# Battery_V2.net
KiCad netlist of a schematic drawn in EAGLE
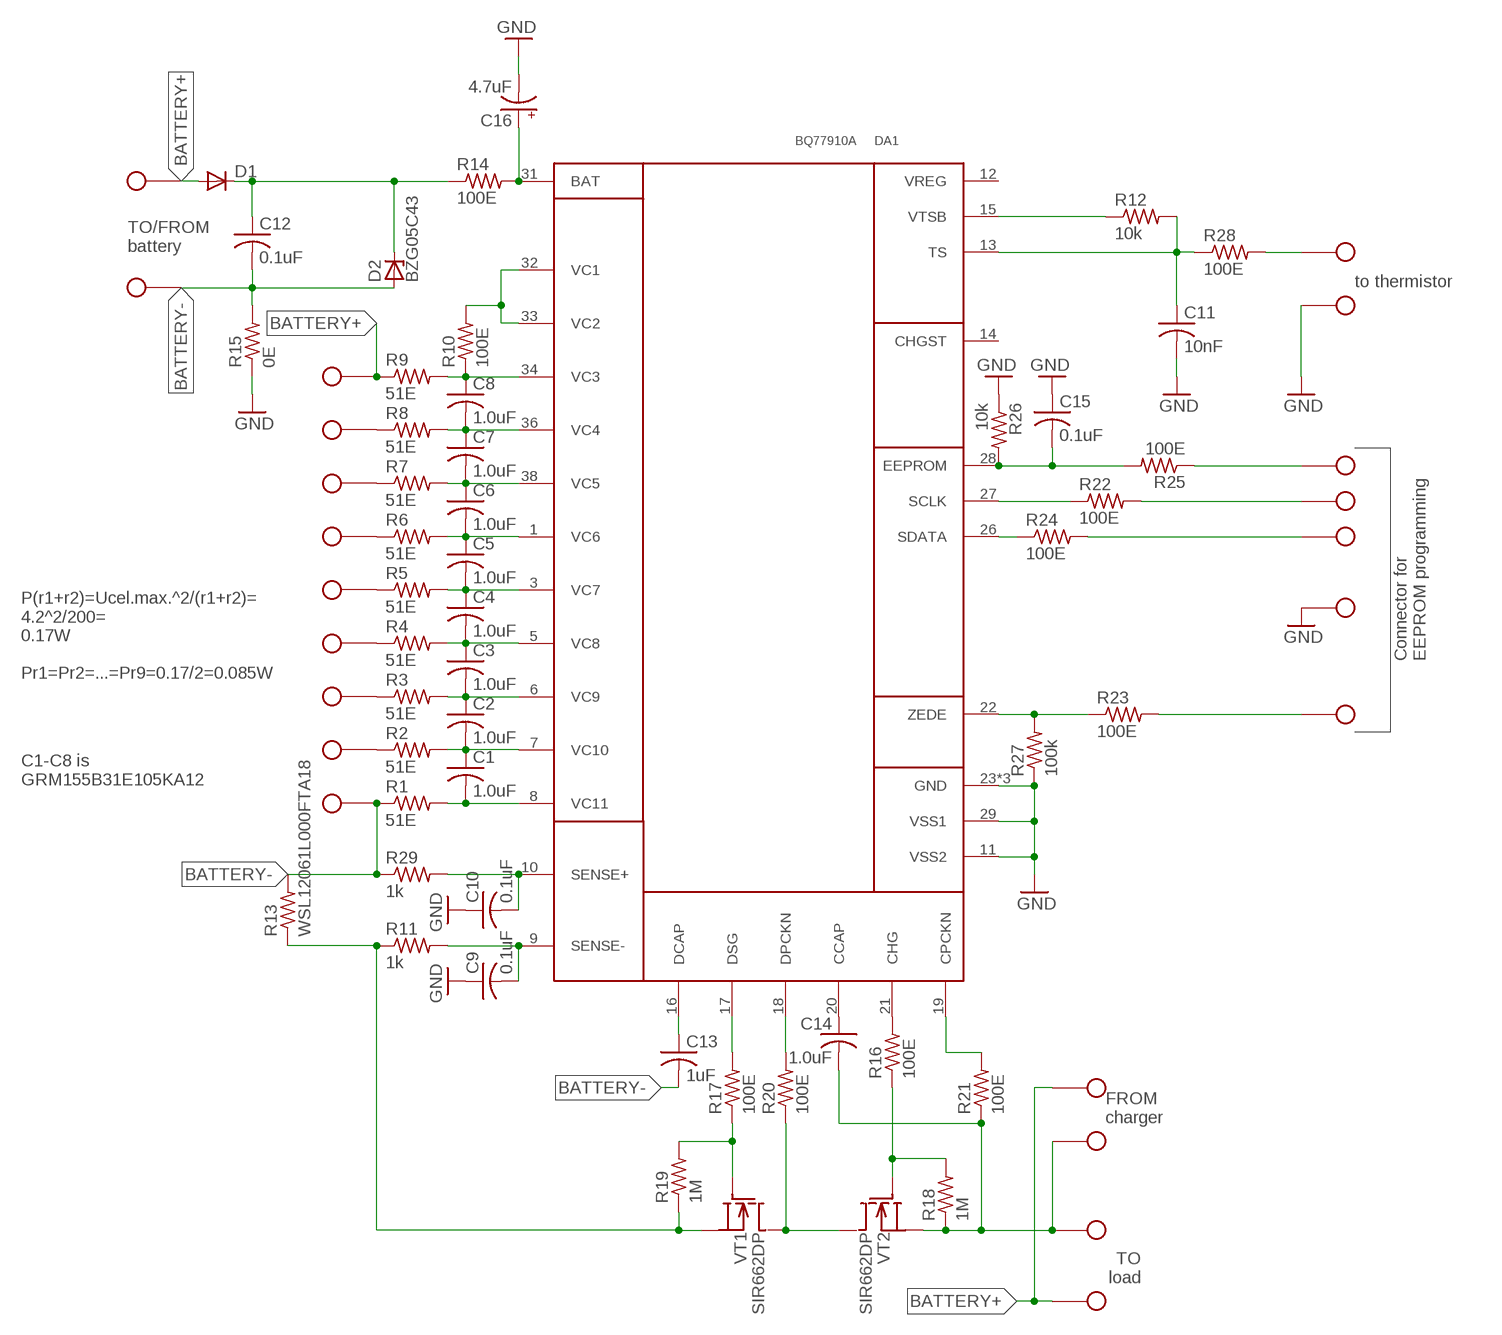
[diagram p0: schematic, sheet 1]

(export (version "E")
  (design (tool "Eeschema 10.0.6"))
  (components
    (comp (ref "C1")
      (value "1.0uF")
      (footprint "eagle-import:C0402K")
      (libsource (lib "eagle-import") (part "C-USC0402K"))
    )
    (comp (ref "C2")
      (value "1.0uF")
      (footprint "eagle-import:C0402K")
      (libsource (lib "eagle-import") (part "C-USC0402K"))
    )
    (comp (ref "C3")
      (value "1.0uF")
      (footprint "eagle-import:C0402K")
      (libsource (lib "eagle-import") (part "C-USC0402K"))
    )
    (comp (ref "C4")
      (value "1.0uF")
      (footprint "eagle-import:C0402K")
      (libsource (lib "eagle-import") (part "C-USC0402K"))
    )
    (comp (ref "C5")
      (value "1.0uF")
      (footprint "eagle-import:C0402K")
      (libsource (lib "eagle-import") (part "C-USC0402K"))
    )
    (comp (ref "C6")
      (value "1.0uF")
      (footprint "eagle-import:C0402K")
      (libsource (lib "eagle-import") (part "C-USC0402K"))
    )
    (comp (ref "C7")
      (value "1.0uF")
      (footprint "eagle-import:C0402K")
      (libsource (lib "eagle-import") (part "C-USC0402K"))
    )
    (comp (ref "C8")
      (value "1.0uF")
      (footprint "eagle-import:C0402K")
      (libsource (lib "eagle-import") (part "C-USC0402K"))
    )
    (comp (ref "C9")
      (value "0.1uF")
      (footprint "eagle-import:C0201")
      (libsource (lib "eagle-import") (part "C-USC0201"))
    )
    (comp (ref "C10")
      (value "0.1uF")
      (footprint "eagle-import:C0201")
      (libsource (lib "eagle-import") (part "C-USC0201"))
    )
    (comp (ref "C11")
      (value "10nF")
      (footprint "eagle-import:C0201")
      (libsource (lib "eagle-import") (part "C-USC0201"))
    )
    (comp (ref "C12")
      (value "0.1uF")
      (footprint "eagle-import:C0402K")
      (libsource (lib "eagle-import") (part "C-USC0402K"))
    )
    (comp (ref "C13")
      (value "1uF")
      (footprint "eagle-import:C0402K")
      (libsource (lib "eagle-import") (part "C-USC0402K"))
    )
    (comp (ref "C14")
      (value "1.0uF")
      (footprint "eagle-import:C0603K")
      (libsource (lib "eagle-import") (part "C-USC0603K"))
    )
    (comp (ref "C15")
      (value "0.1uF")
      (footprint "eagle-import:C0402K")
      (libsource (lib "eagle-import") (part "C-USC0402K"))
    )
    (comp (ref "C16")
      (value "4.7uF")
      (footprint "eagle-import:SMC_P")
      (libsource (lib "eagle-import") (part "CPOL-USSMCP"))
    )
    (comp (ref "D1")
      (value "DIODE-DO-214AC")
      (footprint "eagle-import:DO-214AC")
      (libsource (lib "eagle-import") (part "DIODE-DO-214AC"))
    )
    (comp (ref "D2")
      (value "BZG05C43")
      (footprint "eagle-import:DO-214AC")
      (libsource (lib "eagle-import") (part "ZENER-DIODEDO-214"))
    )
    (comp (ref "DA1")
      (value "BQ77910A")
      (footprint "eagle-import:R-PDSO-G38")
      (libsource (lib "eagle-import") (part "BQ77910A"))
    )
    (comp (ref "R1")
      (value "51E")
      (footprint "eagle-import:M2012")
      (libsource (lib "eagle-import") (part "R-US_M2012"))
    )
    (comp (ref "R2")
      (value "51E")
      (footprint "eagle-import:M2012")
      (libsource (lib "eagle-import") (part "R-US_M2012"))
    )
    (comp (ref "R3")
      (value "51E")
      (footprint "eagle-import:M2012")
      (libsource (lib "eagle-import") (part "R-US_M2012"))
    )
    (comp (ref "R4")
      (value "51E")
      (footprint "eagle-import:M2012")
      (libsource (lib "eagle-import") (part "R-US_M2012"))
    )
    (comp (ref "R5")
      (value "51E")
      (footprint "eagle-import:M2012")
      (libsource (lib "eagle-import") (part "R-US_M2012"))
    )
    (comp (ref "R6")
      (value "51E")
      (footprint "eagle-import:M2012")
      (libsource (lib "eagle-import") (part "R-US_M2012"))
    )
    (comp (ref "R7")
      (value "51E")
      (footprint "eagle-import:M2012")
      (libsource (lib "eagle-import") (part "R-US_M2012"))
    )
    (comp (ref "R8")
      (value "51E")
      (footprint "eagle-import:M2012")
      (libsource (lib "eagle-import") (part "R-US_M2012"))
    )
    (comp (ref "R9")
      (value "51E")
      (footprint "eagle-import:M2012")
      (libsource (lib "eagle-import") (part "R-US_M2012"))
    )
    (comp (ref "R10")
      (value "100E")
      (footprint "eagle-import:R0402")
      (libsource (lib "eagle-import") (part "R-US_R0402"))
    )
    (comp (ref "R11")
      (value "1k")
      (footprint "eagle-import:R0201")
      (libsource (lib "eagle-import") (part "R-US_R0201"))
    )
    (comp (ref "R12")
      (value "10k")
      (footprint "eagle-import:R0201")
      (libsource (lib "eagle-import") (part "R-US_R0201"))
    )
    (comp (ref "R13")
      (value "WSL12061L000FTA18")
      (footprint "eagle-import:R1206")
      (libsource (lib "eagle-import") (part "R-US_R1206"))
    )
    (comp (ref "R14")
      (value "100E")
      (footprint "eagle-import:R0402")
      (libsource (lib "eagle-import") (part "R-US_R0402"))
    )
    (comp (ref "R15")
      (value "0E")
      (footprint "eagle-import:R0402")
      (libsource (lib "eagle-import") (part "R-US_R0402"))
    )
    (comp (ref "R16")
      (value "100E")
      (footprint "eagle-import:R0402")
      (libsource (lib "eagle-import") (part "R-US_R0402"))
    )
    (comp (ref "R17")
      (value "100E")
      (footprint "eagle-import:R0402")
      (libsource (lib "eagle-import") (part "R-US_R0402"))
    )
    (comp (ref "R18")
      (value "1M")
      (footprint "eagle-import:R0402")
      (libsource (lib "eagle-import") (part "R-US_R0402"))
    )
    (comp (ref "R19")
      (value "1M")
      (footprint "eagle-import:R0402")
      (libsource (lib "eagle-import") (part "R-US_R0402"))
    )
    (comp (ref "R20")
      (value "100E")
      (footprint "eagle-import:R0402")
      (libsource (lib "eagle-import") (part "R-US_R0402"))
    )
    (comp (ref "R21")
      (value "100E")
      (footprint "eagle-import:R0402")
      (libsource (lib "eagle-import") (part "R-US_R0402"))
    )
    (comp (ref "R22")
      (value "100E")
      (footprint "eagle-import:R0201")
      (libsource (lib "eagle-import") (part "R-US_R0201"))
    )
    (comp (ref "R23")
      (value "100E")
      (footprint "eagle-import:R0201")
      (libsource (lib "eagle-import") (part "R-US_R0201"))
    )
    (comp (ref "R24")
      (value "100E")
      (footprint "eagle-import:R0201")
      (libsource (lib "eagle-import") (part "R-US_R0201"))
    )
    (comp (ref "R25")
      (value "100E")
      (footprint "eagle-import:R0402")
      (libsource (lib "eagle-import") (part "R-US_R0402"))
    )
    (comp (ref "R26")
      (value "10k")
      (footprint "eagle-import:R0402")
      (libsource (lib "eagle-import") (part "R-US_R0402"))
    )
    (comp (ref "R27")
      (value "100k")
      (footprint "eagle-import:R0201")
      (libsource (lib "eagle-import") (part "R-US_R0201"))
    )
    (comp (ref "R28")
      (value "100E")
      (footprint "eagle-import:R0201")
      (libsource (lib "eagle-import") (part "R-US_R0201"))
    )
    (comp (ref "R29")
      (value "1k")
      (footprint "eagle-import:R0201")
      (libsource (lib "eagle-import") (part "R-US_R0201"))
    )
    (comp (ref "VT1")
      (value "SIR662DP")
      (footprint "eagle-import:POWERPAK_SO8")
      (libsource (lib "eagle-import") (part "SIR662DP"))
    )
    (comp (ref "VT2")
      (value "SIR662DP")
      (footprint "eagle-import:POWERPAK_SO8")
      (libsource (lib "eagle-import") (part "SIR662DP"))
    )
    (comp (ref "X1")
      (value "SOLDER_HOLE24AWG")
      (footprint "eagle-import:SOLDER_HOLE_24")
      (libsource (lib "eagle-import") (part "SOLDER_HOLE24AWG"))
    )
    (comp (ref "X2")
      (value "SOLDER_HOLE24AWG")
      (footprint "eagle-import:SOLDER_HOLE_24")
      (libsource (lib "eagle-import") (part "SOLDER_HOLE24AWG"))
    )
    (comp (ref "X3")
      (value "SOLDER_HOLE24AWG")
      (footprint "eagle-import:SOLDER_HOLE_24")
      (libsource (lib "eagle-import") (part "SOLDER_HOLE24AWG"))
    )
    (comp (ref "X4")
      (value "SOLDER_HOLE24AWG")
      (footprint "eagle-import:SOLDER_HOLE_24")
      (libsource (lib "eagle-import") (part "SOLDER_HOLE24AWG"))
    )
    (comp (ref "X5")
      (value "SOLDER_HOLE24AWG")
      (footprint "eagle-import:SOLDER_HOLE_24")
      (libsource (lib "eagle-import") (part "SOLDER_HOLE24AWG"))
    )
    (comp (ref "X6")
      (value "SOLDER_HOLE24AWG")
      (footprint "eagle-import:SOLDER_HOLE_24")
      (libsource (lib "eagle-import") (part "SOLDER_HOLE24AWG"))
    )
    (comp (ref "X7")
      (value "SOLDER_HOLE24AWG")
      (footprint "eagle-import:SOLDER_HOLE_24")
      (libsource (lib "eagle-import") (part "SOLDER_HOLE24AWG"))
    )
    (comp (ref "X8")
      (value "SOLDER_HOLE24AWG")
      (footprint "eagle-import:SOLDER_HOLE_24")
      (libsource (lib "eagle-import") (part "SOLDER_HOLE24AWG"))
    )
    (comp (ref "X9")
      (value "SOLDER_HOLE24AWG")
      (footprint "eagle-import:SOLDER_HOLE_24")
      (libsource (lib "eagle-import") (part "SOLDER_HOLE24AWG"))
    )
    (comp (ref "X10")
      (value "SOLDER_HOLE24AWG")
      (footprint "eagle-import:SOLDER_HOLE_24")
      (libsource (lib "eagle-import") (part "SOLDER_HOLE24AWG"))
    )
    (comp (ref "X11")
      (value "SOLDER_HOLE24AWG")
      (footprint "eagle-import:SOLDER_HOLE_24")
      (libsource (lib "eagle-import") (part "SOLDER_HOLE24AWG"))
    )
    (comp (ref "X12")
      (value "SOLDER_HOLE18AWG")
      (footprint "eagle-import:SOLDER_HOLE_18")
      (libsource (lib "eagle-import") (part "SOLDER_HOLE18AWG"))
    )
    (comp (ref "X13")
      (value "SOLDER_HOLE18AWG")
      (footprint "eagle-import:SOLDER_HOLE_18")
      (libsource (lib "eagle-import") (part "SOLDER_HOLE18AWG"))
    )
    (comp (ref "X14")
      (value "SOLDER_HOLE18AWG")
      (footprint "eagle-import:SOLDER_HOLE_18")
      (libsource (lib "eagle-import") (part "SOLDER_HOLE18AWG"))
    )
    (comp (ref "X15")
      (value "SOLDER_HOLE18AWG")
      (footprint "eagle-import:SOLDER_HOLE_18")
      (libsource (lib "eagle-import") (part "SOLDER_HOLE18AWG"))
    )
    (comp (ref "X16")
      (value "SOLDER_PAD")
      (footprint "eagle-import:SOLDER_PAD_SMD")
      (libsource (lib "eagle-import") (part "SOLDER_PAD"))
    )
    (comp (ref "X17")
      (value "SOLDER_PAD")
      (footprint "eagle-import:SOLDER_PAD_SMD")
      (libsource (lib "eagle-import") (part "SOLDER_PAD"))
    )
    (comp (ref "X18")
      (value "SOLDER_PAD")
      (footprint "eagle-import:SOLDER_PAD_SMD")
      (libsource (lib "eagle-import") (part "SOLDER_PAD"))
    )
    (comp (ref "X19")
      (value "SOLDER_PAD")
      (footprint "eagle-import:SOLDER_PAD_SMD")
      (libsource (lib "eagle-import") (part "SOLDER_PAD"))
    )
    (comp (ref "X20")
      (value "SOLDER_PAD")
      (footprint "eagle-import:SOLDER_PAD_SMD")
      (libsource (lib "eagle-import") (part "SOLDER_PAD"))
    )
    (comp (ref "X21")
      (value "SOLDER_HOLE24AWG")
      (footprint "eagle-import:SOLDER_HOLE_24")
      (libsource (lib "eagle-import") (part "SOLDER_HOLE24AWG"))
    )
    (comp (ref "X23")
      (value "SOLDER_HOLE24AWG")
      (footprint "eagle-import:SOLDER_HOLE_24")
      (libsource (lib "eagle-import") (part "SOLDER_HOLE24AWG"))
    )
  )
  (nets
    (net (code "1") (name "/VREG") (class "Default")
      (node (ref "DA1") (pin "12") (pinfunction "VREG_12") (pintype "power_in"))
    )
    (net (code "2") (name "BATTERY+") (class "Default")
      (node (ref "D1") (pin "A") (pinfunction "A_A") (pintype "passive"))
      (node (ref "R9") (pin "1") (pinfunction "1_1") (pintype "passive"))
      (node (ref "X1") (pin "1") (pinfunction "P$1_1") (pintype "bidirectional"))
      (node (ref "X11") (pin "1") (pinfunction "P$1_1") (pintype "bidirectional"))
      (node (ref "X12") (pin "1") (pinfunction "P$1_1") (pintype "bidirectional"))
      (node (ref "X15") (pin "1") (pinfunction "P$1_1") (pintype "bidirectional"))
    )
    (net (code "3") (name "BATTERY-") (class "Default")
      (node (ref "C12") (pin "2") (pinfunction "2_2") (pintype "passive"))
      (node (ref "C13") (pin "2") (pinfunction "2_2") (pintype "passive"))
      (node (ref "D2") (pin "A") (pinfunction "A_A") (pintype "passive"))
      (node (ref "R1") (pin "1") (pinfunction "1_1") (pintype "passive"))
      (node (ref "R13") (pin "2") (pinfunction "2_2") (pintype "passive"))
      (node (ref "R15") (pin "2") (pinfunction "2_2") (pintype "passive"))
      (node (ref "R29") (pin "1") (pinfunction "1_1") (pintype "passive"))
      (node (ref "X13") (pin "1") (pinfunction "P$1_1") (pintype "bidirectional"))
      (node (ref "X9") (pin "1") (pinfunction "P$1_1") (pintype "bidirectional"))
    )
    (net (code "4") (name "GND") (class "Default")
      (node (ref "C10") (pin "1") (pinfunction "1_1") (pintype "passive"))
      (node (ref "C11") (pin "2") (pinfunction "2_2") (pintype "passive"))
      (node (ref "C15") (pin "1") (pinfunction "1_1") (pintype "passive"))
      (node (ref "C16") (pin "-") (pinfunction "-_-") (pintype "passive"))
      (node (ref "C9") (pin "1") (pinfunction "1_1") (pintype "passive"))
      (node (ref "DA1") (pin "11") (pinfunction "VSS2_11") (pintype "input"))
      (node (ref "DA1") (pin "23") (pinfunction "GND_23") (pintype "input"))
      (node (ref "DA1") (pin "24") (pinfunction "GND_24") (pintype "input"))
      (node (ref "DA1") (pin "25") (pinfunction "GND_25") (pintype "input"))
      (node (ref "DA1") (pin "29") (pinfunction "VSS1_29") (pintype "input"))
      (node (ref "R15") (pin "1") (pinfunction "1_1") (pintype "passive"))
      (node (ref "R26") (pin "1") (pinfunction "1_1") (pintype "passive"))
      (node (ref "R27") (pin "1") (pinfunction "1_1") (pintype "passive"))
      (node (ref "X20") (pin "P$1") (pinfunction "P$1_P$1") (pintype "bidirectional"))
      (node (ref "X21") (pin "1") (pinfunction "P$1_1") (pintype "bidirectional"))
    )
    (net (code "5") (name "Net-(C12-Pad1)") (class "Default")
      (node (ref "C12") (pin "1") (pinfunction "1_1") (pintype "passive"))
      (node (ref "D1") (pin "C") (pinfunction "C_C") (pintype "passive"))
      (node (ref "D2") (pin "C") (pinfunction "C_C") (pintype "passive"))
      (node (ref "R14") (pin "1") (pinfunction "1_1") (pintype "passive"))
    )
    (net (code "6") (name "Net-(DA1-BAT)") (class "Default")
      (node (ref "C16") (pin "+") (pinfunction "+_+") (pintype "passive"))
      (node (ref "DA1") (pin "31") (pinfunction "BAT_31") (pintype "power_in"))
      (node (ref "R14") (pin "2") (pinfunction "2_2") (pintype "passive"))
    )
    (net (code "7") (name "Net-(DA1-CCAP)") (class "Default")
      (node (ref "C14") (pin "1") (pinfunction "1_1") (pintype "passive"))
      (node (ref "DA1") (pin "20") (pinfunction "CCAP_20") (pintype "input"))
    )
    (net (code "8") (name "Net-(DA1-CHG)") (class "Default")
      (node (ref "DA1") (pin "21") (pinfunction "CHG_21") (pintype "input"))
      (node (ref "R16") (pin "2") (pinfunction "2_2") (pintype "passive"))
    )
    (net (code "9") (name "Net-(DA1-CPCKN)") (class "Default")
      (node (ref "DA1") (pin "19") (pinfunction "CPCKN_19") (pintype "input"))
      (node (ref "R21") (pin "2") (pinfunction "2_2") (pintype "passive"))
    )
    (net (code "10") (name "Net-(DA1-DCAP)") (class "Default")
      (node (ref "C13") (pin "1") (pinfunction "1_1") (pintype "passive"))
      (node (ref "DA1") (pin "16") (pinfunction "DCAP_16") (pintype "input"))
    )
    (net (code "11") (name "Net-(DA1-DPCKN)") (class "Default")
      (node (ref "DA1") (pin "18") (pinfunction "DPCKN_18") (pintype "input"))
      (node (ref "R20") (pin "2") (pinfunction "2_2") (pintype "passive"))
    )
    (net (code "12") (name "Net-(DA1-DSG)") (class "Default")
      (node (ref "DA1") (pin "17") (pinfunction "DSG_17") (pintype "input"))
      (node (ref "R17") (pin "2") (pinfunction "2_2") (pintype "passive"))
    )
    (net (code "13") (name "Net-(DA1-EEPROM)") (class "Default")
      (node (ref "C15") (pin "2") (pinfunction "2_2") (pintype "passive"))
      (node (ref "DA1") (pin "28") (pinfunction "EEPROM_28") (pintype "input"))
      (node (ref "R25") (pin "2") (pinfunction "2_2") (pintype "passive"))
      (node (ref "R26") (pin "2") (pinfunction "2_2") (pintype "passive"))
    )
    (net (code "14") (name "Net-(DA1-SCLK)") (class "Default")
      (node (ref "DA1") (pin "27") (pinfunction "SCLK_27") (pintype "input"))
      (node (ref "R22") (pin "1") (pinfunction "1_1") (pintype "passive"))
    )
    (net (code "15") (name "Net-(DA1-SDATA)") (class "Default")
      (node (ref "DA1") (pin "26") (pinfunction "SDATA_26") (pintype "input"))
      (node (ref "R24") (pin "1") (pinfunction "1_1") (pintype "passive"))
    )
    (net (code "16") (name "Net-(DA1-SENSE+)") (class "Default")
      (node (ref "C10") (pin "2") (pinfunction "2_2") (pintype "passive"))
      (node (ref "DA1") (pin "10") (pinfunction "SENSE+_10") (pintype "input"))
      (node (ref "R29") (pin "2") (pinfunction "2_2") (pintype "passive"))
    )
    (net (code "17") (name "Net-(DA1-SENSE-)") (class "Default")
      (node (ref "C9") (pin "2") (pinfunction "2_2") (pintype "passive"))
      (node (ref "DA1") (pin "9") (pinfunction "SENSE-_9") (pintype "input"))
      (node (ref "R11") (pin "2") (pinfunction "2_2") (pintype "passive"))
    )
    (net (code "18") (name "Net-(DA1-TS)") (class "Default")
      (node (ref "C11") (pin "1") (pinfunction "1_1") (pintype "passive"))
      (node (ref "DA1") (pin "13") (pinfunction "TS_13") (pintype "input"))
      (node (ref "R12") (pin "2") (pinfunction "2_2") (pintype "passive"))
      (node (ref "R28") (pin "1") (pinfunction "1_1") (pintype "passive"))
    )
    (net (code "19") (name "Net-(DA1-VC1)") (class "Default")
      (node (ref "DA1") (pin "32") (pinfunction "VC1_32") (pintype "input"))
      (node (ref "DA1") (pin "33") (pinfunction "VC2_33") (pintype "input"))
      (node (ref "R10") (pin "2") (pinfunction "2_2") (pintype "passive"))
    )
    (net (code "20") (name "Net-(DA1-VC3)") (class "Default")
      (node (ref "C8") (pin "1") (pinfunction "1_1") (pintype "passive"))
      (node (ref "DA1") (pin "34") (pinfunction "VC3_34") (pintype "input"))
      (node (ref "R10") (pin "1") (pinfunction "1_1") (pintype "passive"))
      (node (ref "R9") (pin "2") (pinfunction "2_2") (pintype "passive"))
    )
    (net (code "21") (name "Net-(DA1-VC4)") (class "Default")
      (node (ref "C7") (pin "1") (pinfunction "1_1") (pintype "passive"))
      (node (ref "C8") (pin "2") (pinfunction "2_2") (pintype "passive"))
      (node (ref "DA1") (pin "36") (pinfunction "VC4_36") (pintype "input"))
      (node (ref "R8") (pin "2") (pinfunction "2_2") (pintype "passive"))
    )
    (net (code "22") (name "Net-(DA1-VC5)") (class "Default")
      (node (ref "C6") (pin "1") (pinfunction "1_1") (pintype "passive"))
      (node (ref "C7") (pin "2") (pinfunction "2_2") (pintype "passive"))
      (node (ref "DA1") (pin "38") (pinfunction "VC5_38") (pintype "input"))
      (node (ref "R7") (pin "2") (pinfunction "2_2") (pintype "passive"))
    )
    (net (code "23") (name "Net-(DA1-VC6)") (class "Default")
      (node (ref "C5") (pin "1") (pinfunction "1_1") (pintype "passive"))
      (node (ref "C6") (pin "2") (pinfunction "2_2") (pintype "passive"))
      (node (ref "DA1") (pin "1") (pinfunction "VC6_1") (pintype "input"))
      (node (ref "R6") (pin "2") (pinfunction "2_2") (pintype "passive"))
    )
    (net (code "24") (name "Net-(DA1-VC7)") (class "Default")
      (node (ref "C4") (pin "1") (pinfunction "1_1") (pintype "passive"))
      (node (ref "C5") (pin "2") (pinfunction "2_2") (pintype "passive"))
      (node (ref "DA1") (pin "3") (pinfunction "VC7_3") (pintype "input"))
      (node (ref "R5") (pin "2") (pinfunction "2_2") (pintype "passive"))
    )
    (net (code "25") (name "Net-(DA1-VC8)") (class "Default")
      (node (ref "C3") (pin "1") (pinfunction "1_1") (pintype "passive"))
      (node (ref "C4") (pin "2") (pinfunction "2_2") (pintype "passive"))
      (node (ref "DA1") (pin "5") (pinfunction "VC8_5") (pintype "input"))
      (node (ref "R4") (pin "2") (pinfunction "2_2") (pintype "passive"))
    )
    (net (code "26") (name "Net-(DA1-VC9)") (class "Default")
      (node (ref "C2") (pin "1") (pinfunction "1_1") (pintype "passive"))
      (node (ref "C3") (pin "2") (pinfunction "2_2") (pintype "passive"))
      (node (ref "DA1") (pin "6") (pinfunction "VC9_6") (pintype "input"))
      (node (ref "R3") (pin "2") (pinfunction "2_2") (pintype "passive"))
    )
    (net (code "27") (name "Net-(DA1-VC10)") (class "Default")
      (node (ref "C1") (pin "1") (pinfunction "1_1") (pintype "passive"))
      (node (ref "C2") (pin "2") (pinfunction "2_2") (pintype "passive"))
      (node (ref "DA1") (pin "7") (pinfunction "VC10_7") (pintype "input"))
      (node (ref "R2") (pin "2") (pinfunction "2_2") (pintype "passive"))
    )
    (net (code "28") (name "Net-(DA1-VC11)") (class "Default")
      (node (ref "C1") (pin "2") (pinfunction "2_2") (pintype "passive"))
      (node (ref "DA1") (pin "8") (pinfunction "VC11_8") (pintype "input"))
      (node (ref "R1") (pin "2") (pinfunction "2_2") (pintype "passive"))
    )
    (net (code "29") (name "Net-(DA1-VTSB)") (class "Default")
      (node (ref "DA1") (pin "15") (pinfunction "VTSB_15") (pintype "input"))
      (node (ref "R12") (pin "1") (pinfunction "1_1") (pintype "passive"))
    )
    (net (code "30") (name "Net-(DA1-ZEDE)") (class "Default")
      (node (ref "DA1") (pin "22") (pinfunction "ZEDE_22") (pintype "input"))
      (node (ref "R23") (pin "1") (pinfunction "1_1") (pintype "passive"))
      (node (ref "R27") (pin "2") (pinfunction "2_2") (pintype "passive"))
    )
    (net (code "31") (name "Net-(R11-Pad1)") (class "Default")
      (node (ref "R11") (pin "1") (pinfunction "1_1") (pintype "passive"))
      (node (ref "R13") (pin "1") (pinfunction "1_1") (pintype "passive"))
      (node (ref "R19") (pin "1") (pinfunction "1_1") (pintype "passive"))
      (node (ref "VT1") (pin "S1") (pinfunction "S_S1") (pintype "bidirectional"))
      (node (ref "VT1") (pin "S2") (pinfunction "S_S2") (pintype "bidirectional"))
      (node (ref "VT1") (pin "S3") (pinfunction "S_S3") (pintype "bidirectional"))
    )
    (net (code "32") (name "Net-(R16-Pad1)") (class "Default")
      (node (ref "R16") (pin "1") (pinfunction "1_1") (pintype "passive"))
      (node (ref "R18") (pin "2") (pinfunction "2_2") (pintype "passive"))
      (node (ref "VT2") (pin "G") (pinfunction "G_G") (pintype "bidirectional"))
    )
    (net (code "33") (name "Net-(R17-Pad1)") (class "Default")
      (node (ref "R17") (pin "1") (pinfunction "1_1") (pintype "passive"))
      (node (ref "R19") (pin "2") (pinfunction "2_2") (pintype "passive"))
      (node (ref "VT1") (pin "G") (pinfunction "G_G") (pintype "bidirectional"))
    )
    (net (code "34") (name "Net-(R20-Pad1)") (class "Default")
      (node (ref "R20") (pin "1") (pinfunction "1_1") (pintype "passive"))
      (node (ref "VT1") (pin "D") (pinfunction "D_D") (pintype "bidirectional"))
      (node (ref "VT2") (pin "D") (pinfunction "D_D") (pintype "bidirectional"))
    )
    (net (code "35") (name "Net-(R22-Pad2)") (class "Default")
      (node (ref "R22") (pin "2") (pinfunction "2_2") (pintype "passive"))
      (node (ref "X17") (pin "P$1") (pinfunction "P$1_P$1") (pintype "bidirectional"))
    )
    (net (code "36") (name "Net-(R23-Pad2)") (class "Default")
      (node (ref "R23") (pin "2") (pinfunction "2_2") (pintype "passive"))
      (node (ref "X19") (pin "P$1") (pinfunction "P$1_P$1") (pintype "bidirectional"))
    )
    (net (code "37") (name "Net-(R24-Pad2)") (class "Default")
      (node (ref "R24") (pin "2") (pinfunction "2_2") (pintype "passive"))
      (node (ref "X18") (pin "P$1") (pinfunction "P$1_P$1") (pintype "bidirectional"))
    )
    (net (code "38") (name "Net-(R25-Pad1)") (class "Default")
      (node (ref "R25") (pin "1") (pinfunction "1_1") (pintype "passive"))
      (node (ref "X16") (pin "P$1") (pinfunction "P$1_P$1") (pintype "bidirectional"))
    )
    (net (code "39") (name "Net-(X2-P$1)") (class "Default")
      (node (ref "R8") (pin "1") (pinfunction "1_1") (pintype "passive"))
      (node (ref "X2") (pin "1") (pinfunction "P$1_1") (pintype "bidirectional"))
    )
    (net (code "40") (name "Net-(X3-P$1)") (class "Default")
      (node (ref "R7") (pin "1") (pinfunction "1_1") (pintype "passive"))
      (node (ref "X3") (pin "1") (pinfunction "P$1_1") (pintype "bidirectional"))
    )
    (net (code "41") (name "Net-(X4-P$1)") (class "Default")
      (node (ref "R6") (pin "1") (pinfunction "1_1") (pintype "passive"))
      (node (ref "X4") (pin "1") (pinfunction "P$1_1") (pintype "bidirectional"))
    )
    (net (code "42") (name "Net-(X5-P$1)") (class "Default")
      (node (ref "R5") (pin "1") (pinfunction "1_1") (pintype "passive"))
      (node (ref "X5") (pin "1") (pinfunction "P$1_1") (pintype "bidirectional"))
    )
    (net (code "43") (name "Net-(X6-P$1)") (class "Default")
      (node (ref "R4") (pin "1") (pinfunction "1_1") (pintype "passive"))
      (node (ref "X6") (pin "1") (pinfunction "P$1_1") (pintype "bidirectional"))
    )
    (net (code "44") (name "Net-(X7-P$1)") (class "Default")
      (node (ref "R3") (pin "1") (pinfunction "1_1") (pintype "passive"))
      (node (ref "X7") (pin "1") (pinfunction "P$1_1") (pintype "bidirectional"))
    )
    (net (code "45") (name "Net-(X8-P$1)") (class "Default")
      (node (ref "R2") (pin "1") (pinfunction "1_1") (pintype "passive"))
      (node (ref "X8") (pin "1") (pinfunction "P$1_1") (pintype "bidirectional"))
    )
    (net (code "46") (name "Net-(X10-P$1)") (class "Default")
      (node (ref "C14") (pin "2") (pinfunction "2_2") (pintype "passive"))
      (node (ref "R18") (pin "1") (pinfunction "1_1") (pintype "passive"))
      (node (ref "R21") (pin "1") (pinfunction "1_1") (pintype "passive"))
      (node (ref "VT2") (pin "S1") (pinfunction "S_S1") (pintype "bidirectional"))
      (node (ref "VT2") (pin "S2") (pinfunction "S_S2") (pintype "bidirectional"))
      (node (ref "VT2") (pin "S3") (pinfunction "S_S3") (pintype "bidirectional"))
      (node (ref "X10") (pin "1") (pinfunction "P$1_1") (pintype "bidirectional"))
      (node (ref "X14") (pin "1") (pinfunction "P$1_1") (pintype "bidirectional"))
    )
    (net (code "47") (name "Net-(X23-P$1)") (class "Default")
      (node (ref "R28") (pin "2") (pinfunction "2_2") (pintype "passive"))
      (node (ref "X23") (pin "1") (pinfunction "P$1_1") (pintype "bidirectional"))
    )
    (net (code "48") (name "unconnected-(DA1-1-Pad2)") (class "Default")
      (node (ref "DA1") (pin "2") (pinfunction "1_2") (pintype "no_connect"))
    )
    (net (code "49") (name "unconnected-(DA1-2-Pad4)") (class "Default")
      (node (ref "DA1") (pin "4") (pinfunction "2_4") (pintype "no_connect"))
    )
    (net (code "50") (name "unconnected-(DA1-3-Pad30)") (class "Default")
      (node (ref "DA1") (pin "30") (pinfunction "3_30") (pintype "no_connect"))
    )
    (net (code "51") (name "unconnected-(DA1-4-Pad35)") (class "Default")
      (node (ref "DA1") (pin "35") (pinfunction "4_35") (pintype "no_connect"))
    )
    (net (code "52") (name "unconnected-(DA1-5-Pad37)") (class "Default")
      (node (ref "DA1") (pin "37") (pinfunction "5_37") (pintype "no_connect"))
    )
    (net (code "53") (name "unconnected-(DA1-CHGST-Pad14)") (class "Default")
      (node (ref "DA1") (pin "14") (pinfunction "CHGST_14") (pintype "input"))
    )
  )
)
